# TSMP-TS.net
KiCad netlist of a schematic drawn in EAGLE
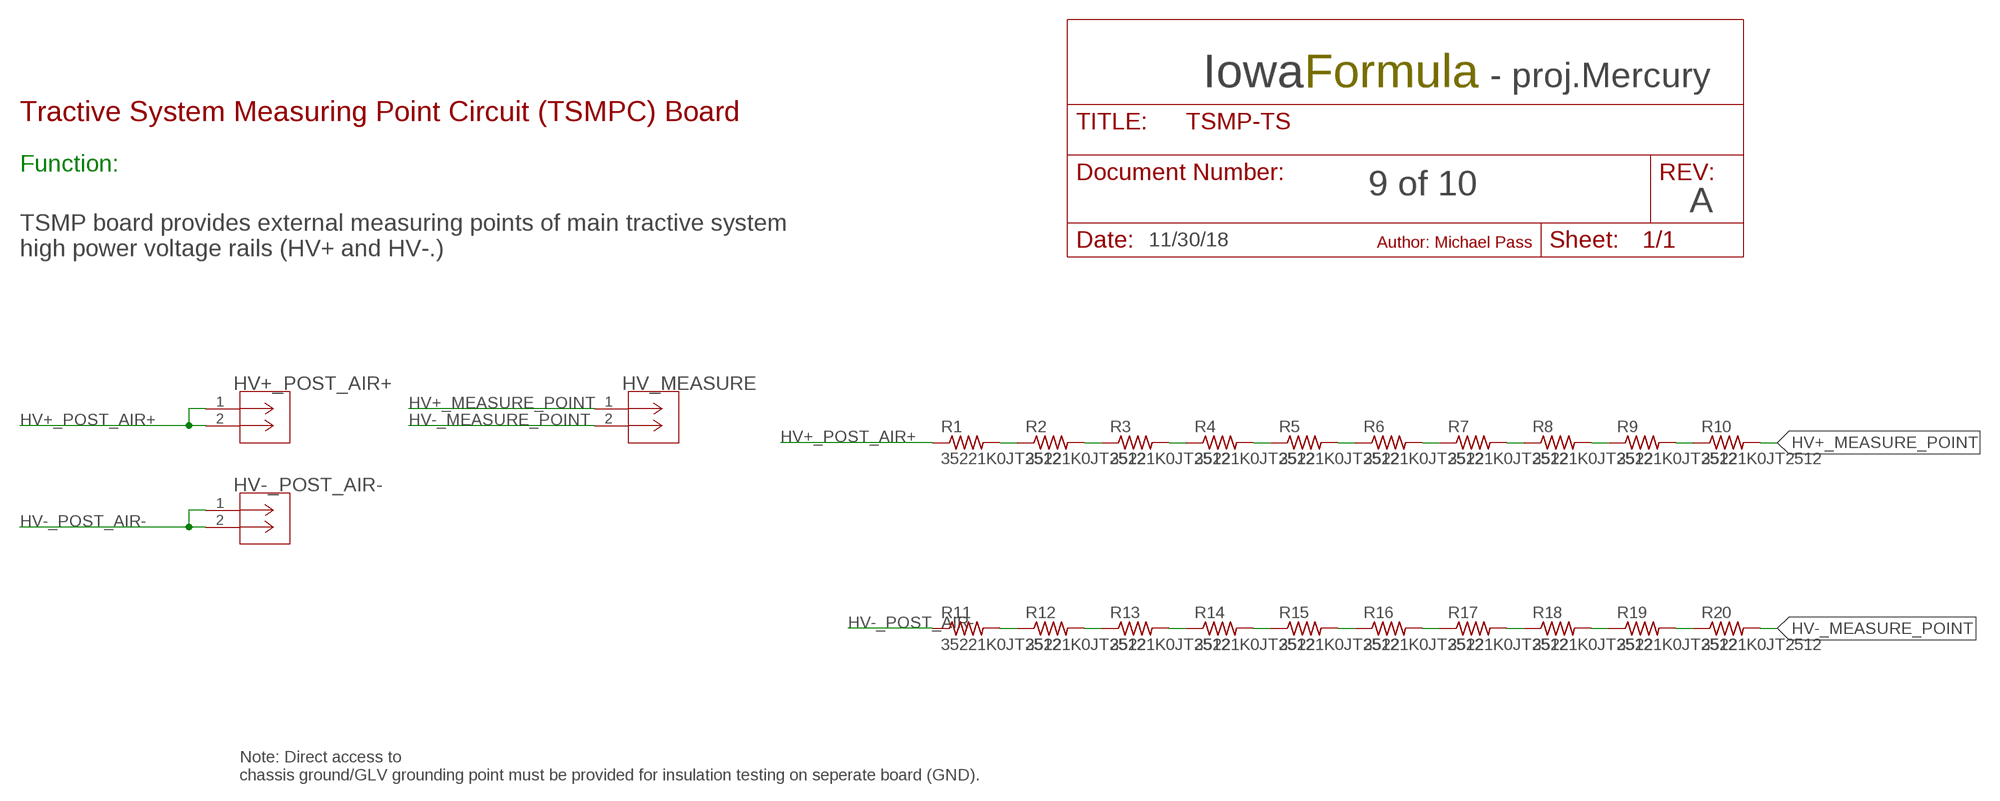
[diagram p0: schematic, sheet 1]

(export (version "E")
  (design (tool "Eeschema 10.0.6"))
  (components
    (comp (ref "HV+_POST_AIR+")
      (value "2P_1-770166-0")
      (footprint "eagle-import:CON2_1X2_P163_VMNL-1MTG")
      (fields (field (name "MANUFACTURER_PART_NUMBER") "17701660"))
      (libsource (lib "eagle-import") (part "2P_1-770166-0"))
    )
    (comp (ref "HV-_POST_AIR-")
      (value "2P_1-770166-0")
      (footprint "eagle-import:CON2_1X2_P163_VMNL-1MTG")
      (fields (field (name "MANUFACTURER_PART_NUMBER") "17701660"))
      (libsource (lib "eagle-import") (part "2P_1-770166-0"))
    )
    (comp (ref "HV_MEASURE")
      (value "2P_1-770166-0")
      (footprint "eagle-import:CON2_1X2_P163_VMNL-1MTG")
      (fields (field (name "MANUFACTURER_PART_NUMBER") "17701660"))
      (libsource (lib "eagle-import") (part "2P_1-770166-0"))
    )
    (comp (ref "R1")
      (value "35221K0JT2512")
      (footprint "eagle-import:R2512")
      (libsource (lib "eagle-import") (part "35221K0JT2512"))
    )
    (comp (ref "R2")
      (value "35221K0JT2512")
      (footprint "eagle-import:R2512")
      (libsource (lib "eagle-import") (part "35221K0JT2512"))
    )
    (comp (ref "R3")
      (value "35221K0JT2512")
      (footprint "eagle-import:R2512")
      (libsource (lib "eagle-import") (part "35221K0JT2512"))
    )
    (comp (ref "R4")
      (value "35221K0JT2512")
      (footprint "eagle-import:R2512")
      (libsource (lib "eagle-import") (part "35221K0JT2512"))
    )
    (comp (ref "R5")
      (value "35221K0JT2512")
      (footprint "eagle-import:R2512")
      (libsource (lib "eagle-import") (part "35221K0JT2512"))
    )
    (comp (ref "R6")
      (value "35221K0JT2512")
      (footprint "eagle-import:R2512")
      (libsource (lib "eagle-import") (part "35221K0JT2512"))
    )
    (comp (ref "R7")
      (value "35221K0JT2512")
      (footprint "eagle-import:R2512")
      (libsource (lib "eagle-import") (part "35221K0JT2512"))
    )
    (comp (ref "R8")
      (value "35221K0JT2512")
      (footprint "eagle-import:R2512")
      (libsource (lib "eagle-import") (part "35221K0JT2512"))
    )
    (comp (ref "R9")
      (value "35221K0JT2512")
      (footprint "eagle-import:R2512")
      (libsource (lib "eagle-import") (part "35221K0JT2512"))
    )
    (comp (ref "R10")
      (value "35221K0JT2512")
      (footprint "eagle-import:R2512")
      (libsource (lib "eagle-import") (part "35221K0JT2512"))
    )
    (comp (ref "R11")
      (value "35221K0JT2512")
      (footprint "eagle-import:R2512")
      (libsource (lib "eagle-import") (part "35221K0JT2512"))
    )
    (comp (ref "R12")
      (value "35221K0JT2512")
      (footprint "eagle-import:R2512")
      (libsource (lib "eagle-import") (part "35221K0JT2512"))
    )
    (comp (ref "R13")
      (value "35221K0JT2512")
      (footprint "eagle-import:R2512")
      (libsource (lib "eagle-import") (part "35221K0JT2512"))
    )
    (comp (ref "R14")
      (value "35221K0JT2512")
      (footprint "eagle-import:R2512")
      (libsource (lib "eagle-import") (part "35221K0JT2512"))
    )
    (comp (ref "R15")
      (value "35221K0JT2512")
      (footprint "eagle-import:R2512")
      (libsource (lib "eagle-import") (part "35221K0JT2512"))
    )
    (comp (ref "R16")
      (value "35221K0JT2512")
      (footprint "eagle-import:R2512")
      (libsource (lib "eagle-import") (part "35221K0JT2512"))
    )
    (comp (ref "R17")
      (value "35221K0JT2512")
      (footprint "eagle-import:R2512")
      (libsource (lib "eagle-import") (part "35221K0JT2512"))
    )
    (comp (ref "R18")
      (value "35221K0JT2512")
      (footprint "eagle-import:R2512")
      (libsource (lib "eagle-import") (part "35221K0JT2512"))
    )
    (comp (ref "R19")
      (value "35221K0JT2512")
      (footprint "eagle-import:R2512")
      (libsource (lib "eagle-import") (part "35221K0JT2512"))
    )
    (comp (ref "R20")
      (value "35221K0JT2512")
      (footprint "eagle-import:R2512")
      (libsource (lib "eagle-import") (part "35221K0JT2512"))
    )
  )
  (nets
    (net (code "1") (name "/HV+_POST_AIR+") (class "Default")
      (node (ref "HV+_POST_AIR+") (pin "1") (pinfunction "1_1") (pintype "passive"))
      (node (ref "HV+_POST_AIR+") (pin "2") (pinfunction "2_2") (pintype "passive"))
      (node (ref "R1") (pin "1") (pinfunction "1_1") (pintype "passive"))
    )
    (net (code "2") (name "/HV-_POST_AIR-") (class "Default")
      (node (ref "HV-_POST_AIR-") (pin "1") (pinfunction "1_1") (pintype "passive"))
      (node (ref "HV-_POST_AIR-") (pin "2") (pinfunction "2_2") (pintype "passive"))
      (node (ref "R11") (pin "1") (pinfunction "1_1") (pintype "passive"))
    )
    (net (code "3") (name "HV+_MEASURE_POINT") (class "Default")
      (node (ref "HV_MEASURE") (pin "1") (pinfunction "1_1") (pintype "passive"))
      (node (ref "R10") (pin "2") (pinfunction "2_2") (pintype "passive"))
    )
    (net (code "4") (name "HV-_MEASURE_POINT") (class "Default")
      (node (ref "HV_MEASURE") (pin "2") (pinfunction "2_2") (pintype "passive"))
      (node (ref "R20") (pin "2") (pinfunction "2_2") (pintype "passive"))
    )
    (net (code "5") (name "Net-(R1-Pad2)") (class "Default")
      (node (ref "R1") (pin "2") (pinfunction "2_2") (pintype "passive"))
      (node (ref "R2") (pin "1") (pinfunction "1_1") (pintype "passive"))
    )
    (net (code "6") (name "Net-(R2-Pad2)") (class "Default")
      (node (ref "R2") (pin "2") (pinfunction "2_2") (pintype "passive"))
      (node (ref "R3") (pin "1") (pinfunction "1_1") (pintype "passive"))
    )
    (net (code "7") (name "Net-(R3-Pad2)") (class "Default")
      (node (ref "R3") (pin "2") (pinfunction "2_2") (pintype "passive"))
      (node (ref "R4") (pin "1") (pinfunction "1_1") (pintype "passive"))
    )
    (net (code "8") (name "Net-(R4-Pad2)") (class "Default")
      (node (ref "R4") (pin "2") (pinfunction "2_2") (pintype "passive"))
      (node (ref "R5") (pin "1") (pinfunction "1_1") (pintype "passive"))
    )
    (net (code "9") (name "Net-(R5-Pad2)") (class "Default")
      (node (ref "R5") (pin "2") (pinfunction "2_2") (pintype "passive"))
      (node (ref "R6") (pin "1") (pinfunction "1_1") (pintype "passive"))
    )
    (net (code "10") (name "Net-(R6-Pad2)") (class "Default")
      (node (ref "R6") (pin "2") (pinfunction "2_2") (pintype "passive"))
      (node (ref "R7") (pin "1") (pinfunction "1_1") (pintype "passive"))
    )
    (net (code "11") (name "Net-(R7-Pad2)") (class "Default")
      (node (ref "R7") (pin "2") (pinfunction "2_2") (pintype "passive"))
      (node (ref "R8") (pin "1") (pinfunction "1_1") (pintype "passive"))
    )
    (net (code "12") (name "Net-(R8-Pad2)") (class "Default")
      (node (ref "R8") (pin "2") (pinfunction "2_2") (pintype "passive"))
      (node (ref "R9") (pin "1") (pinfunction "1_1") (pintype "passive"))
    )
    (net (code "13") (name "Net-(R10-Pad1)") (class "Default")
      (node (ref "R10") (pin "1") (pinfunction "1_1") (pintype "passive"))
      (node (ref "R9") (pin "2") (pinfunction "2_2") (pintype "passive"))
    )
    (net (code "14") (name "Net-(R11-Pad2)") (class "Default")
      (node (ref "R11") (pin "2") (pinfunction "2_2") (pintype "passive"))
      (node (ref "R12") (pin "1") (pinfunction "1_1") (pintype "passive"))
    )
    (net (code "15") (name "Net-(R12-Pad2)") (class "Default")
      (node (ref "R12") (pin "2") (pinfunction "2_2") (pintype "passive"))
      (node (ref "R13") (pin "1") (pinfunction "1_1") (pintype "passive"))
    )
    (net (code "16") (name "Net-(R13-Pad2)") (class "Default")
      (node (ref "R13") (pin "2") (pinfunction "2_2") (pintype "passive"))
      (node (ref "R14") (pin "1") (pinfunction "1_1") (pintype "passive"))
    )
    (net (code "17") (name "Net-(R14-Pad2)") (class "Default")
      (node (ref "R14") (pin "2") (pinfunction "2_2") (pintype "passive"))
      (node (ref "R15") (pin "1") (pinfunction "1_1") (pintype "passive"))
    )
    (net (code "18") (name "Net-(R15-Pad2)") (class "Default")
      (node (ref "R15") (pin "2") (pinfunction "2_2") (pintype "passive"))
      (node (ref "R16") (pin "1") (pinfunction "1_1") (pintype "passive"))
    )
    (net (code "19") (name "Net-(R16-Pad2)") (class "Default")
      (node (ref "R16") (pin "2") (pinfunction "2_2") (pintype "passive"))
      (node (ref "R17") (pin "1") (pinfunction "1_1") (pintype "passive"))
    )
    (net (code "20") (name "Net-(R17-Pad2)") (class "Default")
      (node (ref "R17") (pin "2") (pinfunction "2_2") (pintype "passive"))
      (node (ref "R18") (pin "1") (pinfunction "1_1") (pintype "passive"))
    )
    (net (code "21") (name "Net-(R18-Pad2)") (class "Default")
      (node (ref "R18") (pin "2") (pinfunction "2_2") (pintype "passive"))
      (node (ref "R19") (pin "1") (pinfunction "1_1") (pintype "passive"))
    )
    (net (code "22") (name "Net-(R19-Pad2)") (class "Default")
      (node (ref "R19") (pin "2") (pinfunction "2_2") (pintype "passive"))
      (node (ref "R20") (pin "1") (pinfunction "1_1") (pintype "passive"))
    )
  )
)
